# Schematic.net
KiCad netlist of a schematic drawn in Altium Designer
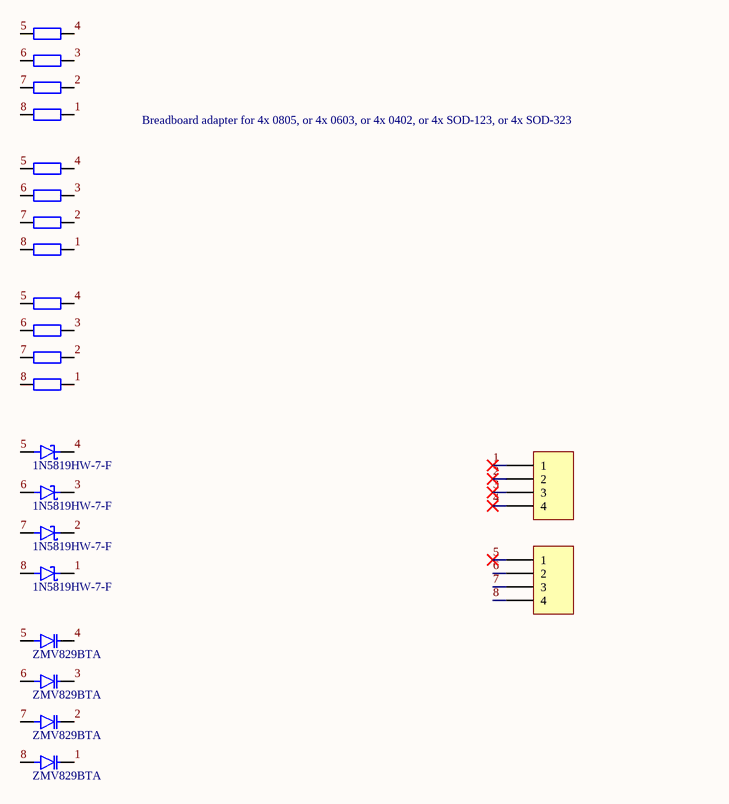
[diagram p0: Schematic.SchDoc]

(export (version "E")
  (design (tool "Eeschema 10.0.6"))
  (components
    (comp (ref "D1")
      (value "1N5819HW-7-F")
      (footprint "SOD3715X145N")
      (description "Diode Schottky 40 V 1A Surface Mount SOD-123")
      (fields (field (name "MF") "Diodes Inc."))
      (libsource (lib "1N5819HW-7-F") (part "1N5819HW-7-F"))
    )
    (comp (ref "D2")
      (value "1N5819HW-7-F")
      (footprint "SOD3715X145N")
      (description "Diode Schottky 40 V 1A Surface Mount SOD-123")
      (fields (field (name "MF") "Diodes Inc."))
      (libsource (lib "1N5819HW-7-F") (part "1N5819HW-7-F"))
    )
    (comp (ref "D3")
      (value "1N5819HW-7-F")
      (footprint "SOD3715X145N")
      (description "Diode Schottky 40 V 1A Surface Mount SOD-123")
      (fields (field (name "MF") "Diodes Inc."))
      (libsource (lib "1N5819HW-7-F") (part "1N5819HW-7-F"))
    )
    (comp (ref "D4")
      (value "1N5819HW-7-F")
      (footprint "SOD3715X145N")
      (description "Diode Schottky 40 V 1A Surface Mount SOD-123")
      (fields (field (name "MF") "Diodes Inc."))
      (libsource (lib "1N5819HW-7-F") (part "1N5819HW-7-F"))
    )
    (comp (ref "D5")
      (value "ZMV829BTA")
      (footprint "SOD2512X116N")
      (description "Varactors Single 25 V Surface Mount SOD-323")
      (fields (field (name "MF") "Diodes Inc."))
      (libsource (lib "ZMV829BTA") (part "ZMV829BTA"))
    )
    (comp (ref "D6")
      (value "ZMV829BTA")
      (footprint "SOD2512X116N")
      (description "Varactors Single 25 V Surface Mount SOD-323")
      (fields (field (name "MF") "Diodes Inc."))
      (libsource (lib "ZMV829BTA") (part "ZMV829BTA"))
    )
    (comp (ref "D7")
      (value "ZMV829BTA")
      (footprint "SOD2512X116N")
      (description "Varactors Single 25 V Surface Mount SOD-323")
      (fields (field (name "MF") "Diodes Inc."))
      (libsource (lib "ZMV829BTA") (part "ZMV829BTA"))
    )
    (comp (ref "D8")
      (value "ZMV829BTA")
      (footprint "SOD2512X116N")
      (description "Varactors Single 25 V Surface Mount SOD-323")
      (fields (field (name "MF") "Diodes Inc."))
      (libsource (lib "ZMV829BTA") (part "ZMV829BTA"))
    )
    (comp (ref "P1")
      (value "Header 4")
      (footprint "HDR1X4")
      (description "Header, 4-Pin")
      (fields (field (name "PUBLISHER") "Altium Limited"))
      (libsource (lib "Miscellaneous Connectors") (part "Header 4"))
    )
    (comp (ref "P2")
      (value "Header 4")
      (footprint "HDR1X4")
      (description "Header, 4-Pin")
      (fields (field (name "PUBLISHER") "Altium Limited"))
      (libsource (lib "Miscellaneous Connectors") (part "Header 4"))
    )
    (comp (ref "R1")
      (value "~")
      (footprint "0805")
      (description "Resistor")
      (libsource (lib "General Components") (part "Res 0805"))
    )
    (comp (ref "R2")
      (value "~")
      (footprint "0805")
      (description "Resistor")
      (libsource (lib "General Components") (part "Res 0805"))
    )
    (comp (ref "R3")
      (value "~")
      (footprint "0805")
      (description "Resistor")
      (libsource (lib "General Components") (part "Res 0805"))
    )
    (comp (ref "R4")
      (value "~")
      (footprint "0805")
      (description "Resistor")
      (libsource (lib "General Components") (part "Res 0805"))
    )
    (comp (ref "R5")
      (value "~")
      (footprint "J1-0603")
      (description "Resistor")
      (libsource (lib "General Components") (part "Res 0402"))
    )
    (comp (ref "R6")
      (value "~")
      (footprint "J1-0603")
      (description "Resistor")
      (libsource (lib "General Components") (part "Res 0402"))
    )
    (comp (ref "R7")
      (value "~")
      (footprint "J1-0603")
      (description "Resistor")
      (libsource (lib "General Components") (part "Res 0402"))
    )
    (comp (ref "R8")
      (value "~")
      (footprint "J1-0603")
      (description "Resistor")
      (libsource (lib "General Components") (part "Res 0402"))
    )
    (comp (ref "R9")
      (value "~")
      (footprint "RES 0402")
      (description "Resistor")
      (libsource (lib "General Components") (part "Res 0805"))
    )
    (comp (ref "R10")
      (value "~")
      (footprint "RES 0402")
      (description "Resistor")
      (libsource (lib "General Components") (part "Res 0805"))
    )
    (comp (ref "R11")
      (value "~")
      (footprint "RES 0402")
      (description "Resistor")
      (libsource (lib "General Components") (part "Res 0805"))
    )
    (comp (ref "R12")
      (value "~")
      (footprint "RES 0402")
      (description "Resistor")
      (libsource (lib "General Components") (part "Res 0805"))
    )
  )
  (nets
    (net (code "1") (name "/1") (class "Default")
      (node (ref "D4") (pin "C") (pinfunction "K_C") (pintype "passive"))
      (node (ref "D8") (pin "K") (pinfunction "K_K") (pintype "passive"))
      (node (ref "P1") (pin "1") (pinfunction "1_1") (pintype "passive"))
      (node (ref "R12") (pin "2") (pinfunction "2_2") (pintype "passive"))
      (node (ref "R4") (pin "2") (pinfunction "2_2") (pintype "passive"))
      (node (ref "R8") (pin "2") (pinfunction "2_2") (pintype "passive"))
    )
    (net (code "2") (name "/2") (class "Default")
      (node (ref "D3") (pin "C") (pinfunction "K_C") (pintype "passive"))
      (node (ref "D7") (pin "K") (pinfunction "K_K") (pintype "passive"))
      (node (ref "P1") (pin "2") (pinfunction "2_2") (pintype "passive"))
      (node (ref "R11") (pin "2") (pinfunction "2_2") (pintype "passive"))
      (node (ref "R3") (pin "2") (pinfunction "2_2") (pintype "passive"))
      (node (ref "R7") (pin "2") (pinfunction "2_2") (pintype "passive"))
    )
    (net (code "3") (name "/3") (class "Default")
      (node (ref "D2") (pin "C") (pinfunction "K_C") (pintype "passive"))
      (node (ref "D6") (pin "K") (pinfunction "K_K") (pintype "passive"))
      (node (ref "P1") (pin "3") (pinfunction "3_3") (pintype "passive"))
      (node (ref "R10") (pin "2") (pinfunction "2_2") (pintype "passive"))
      (node (ref "R2") (pin "2") (pinfunction "2_2") (pintype "passive"))
      (node (ref "R6") (pin "2") (pinfunction "2_2") (pintype "passive"))
    )
    (net (code "4") (name "/4") (class "Default")
      (node (ref "D1") (pin "C") (pinfunction "K_C") (pintype "passive"))
      (node (ref "D5") (pin "K") (pinfunction "K_K") (pintype "passive"))
      (node (ref "P1") (pin "4") (pinfunction "4_4") (pintype "passive"))
      (node (ref "R1") (pin "2") (pinfunction "2_2") (pintype "passive"))
      (node (ref "R5") (pin "2") (pinfunction "2_2") (pintype "passive"))
      (node (ref "R9") (pin "2") (pinfunction "2_2") (pintype "passive"))
    )
    (net (code "5") (name "/5") (class "Default")
      (node (ref "D1") (pin "A") (pinfunction "A_A") (pintype "passive"))
      (node (ref "D5") (pin "A") (pinfunction "A_A") (pintype "passive"))
      (node (ref "P2") (pin "1") (pinfunction "1_1") (pintype "passive"))
      (node (ref "R1") (pin "1") (pinfunction "1_1") (pintype "passive"))
      (node (ref "R5") (pin "1") (pinfunction "1_1") (pintype "passive"))
      (node (ref "R9") (pin "1") (pinfunction "1_1") (pintype "passive"))
    )
    (net (code "6") (name "/6") (class "Default")
      (node (ref "D2") (pin "A") (pinfunction "A_A") (pintype "passive"))
      (node (ref "D6") (pin "A") (pinfunction "A_A") (pintype "passive"))
      (node (ref "P2") (pin "2") (pinfunction "2_2") (pintype "passive"))
      (node (ref "R10") (pin "1") (pinfunction "1_1") (pintype "passive"))
      (node (ref "R2") (pin "1") (pinfunction "1_1") (pintype "passive"))
      (node (ref "R6") (pin "1") (pinfunction "1_1") (pintype "passive"))
    )
    (net (code "7") (name "/7") (class "Default")
      (node (ref "D3") (pin "A") (pinfunction "A_A") (pintype "passive"))
      (node (ref "D7") (pin "A") (pinfunction "A_A") (pintype "passive"))
      (node (ref "P2") (pin "3") (pinfunction "3_3") (pintype "passive"))
      (node (ref "R11") (pin "1") (pinfunction "1_1") (pintype "passive"))
      (node (ref "R3") (pin "1") (pinfunction "1_1") (pintype "passive"))
      (node (ref "R7") (pin "1") (pinfunction "1_1") (pintype "passive"))
    )
    (net (code "8") (name "/8") (class "Default")
      (node (ref "D4") (pin "A") (pinfunction "A_A") (pintype "passive"))
      (node (ref "D8") (pin "A") (pinfunction "A_A") (pintype "passive"))
      (node (ref "P2") (pin "4") (pinfunction "4_4") (pintype "passive"))
      (node (ref "R12") (pin "1") (pinfunction "1_1") (pintype "passive"))
      (node (ref "R4") (pin "1") (pinfunction "1_1") (pintype "passive"))
      (node (ref "R8") (pin "1") (pinfunction "1_1") (pintype "passive"))
    )
  )
)
